# STM32F070CBT6.net
KiCad netlist of a schematic drawn in Altium Designer
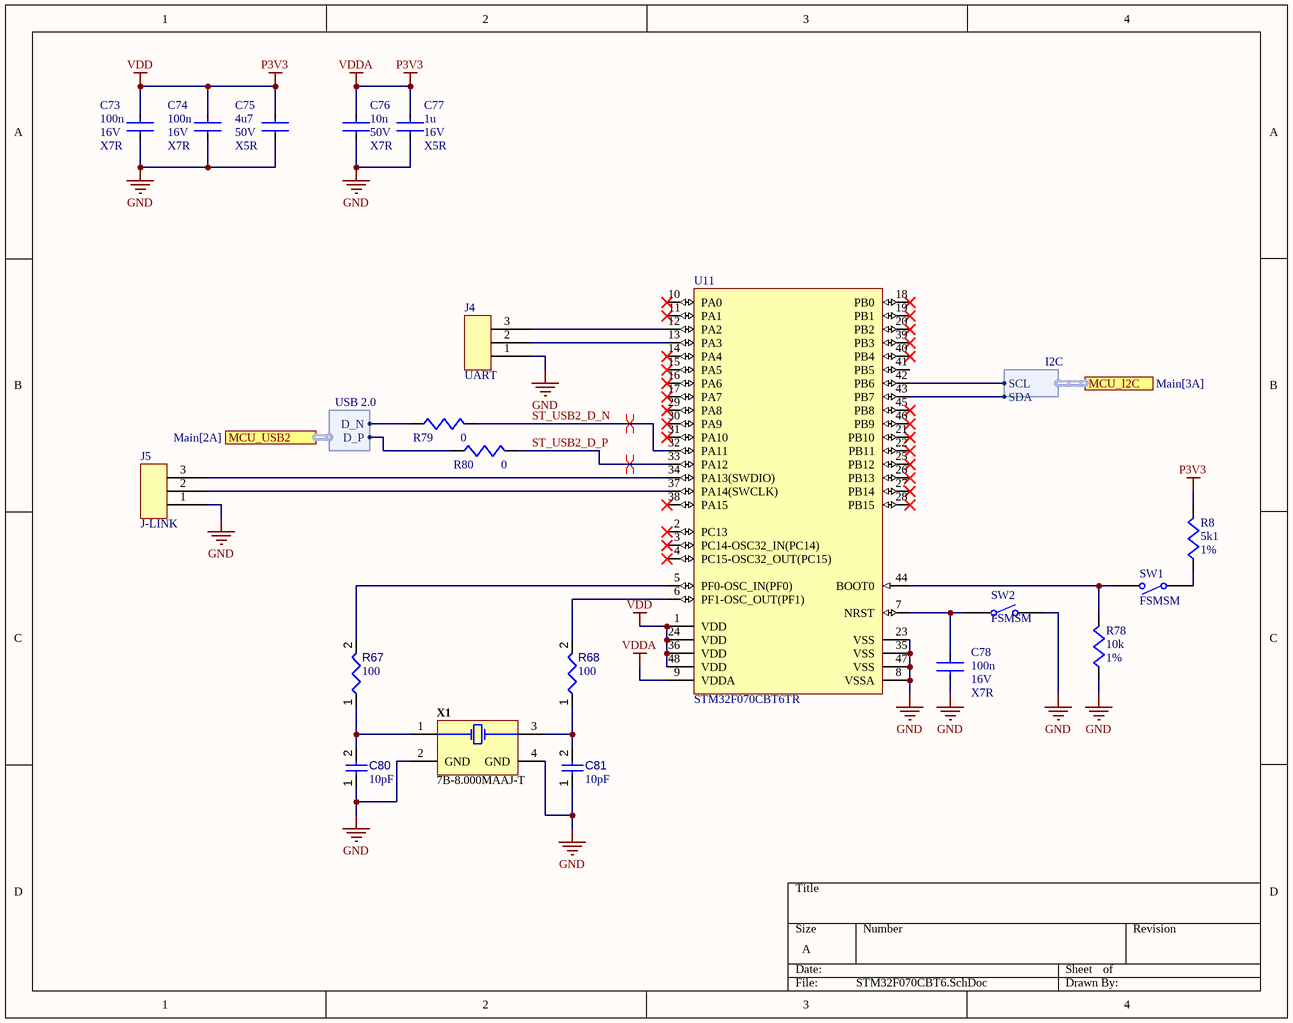
[diagram p0: STM32F070CBT6.SchDoc]

(export (version "E")
  (design (tool "Eeschema 10.0.6"))
  (components
    (comp (ref "C73")
      (value "100n")
      (footprint "CAPC1005X06N")
      (description "16V 100nF X7R ±10% 0402 Multilayer Ceramic Capacitors MLCC - SMD/SMT ROHS")
      (fields
        (field (name "VOLTAGE") "16V")
        (field (name "DIELECTRIC") "X7R")
        (field (name "LCSC PART #") "C1525")
        (field (name "Comment") "100nF 16V 0402")
      )
      (libsource (lib "CWRU Motorsports") (part "Capacitor"))
    )
    (comp (ref "C74")
      (value "100n")
      (footprint "CAPC1005X06N")
      (description "16V 100nF X7R ±10% 0402 Multilayer Ceramic Capacitors MLCC - SMD/SMT ROHS")
      (fields
        (field (name "VOLTAGE") "16V")
        (field (name "DIELECTRIC") "X7R")
        (field (name "LCSC PART #") "C1525")
        (field (name "Comment") "100nF 16V 0402")
      )
      (libsource (lib "CWRU Motorsports") (part "Capacitor"))
    )
    (comp (ref "C75")
      (value "4u7")
      (footprint "CAPC2012X14N")
      (description "50V 4.7uF X5R ±10% 0805 Multilayer Ceramic Capacitors MLCC - SMD/SMT ROHS")
      (fields
        (field (name "VOLTAGE") "50V")
        (field (name "DIELECTRIC") "X5R")
        (field (name "LCSC PART #") "C98192")
        (field (name "Comment") "4.7uF 50V 0805")
      )
      (libsource (lib "CWRU Motorsports") (part "Capacitor"))
    )
    (comp (ref "C76")
      (value "10n")
      (footprint "CAPC1608X08N")
      (description "50V 10nF X7R ±10% 0603 Multilayer Ceramic Capacitors MLCC - SMD/SMT ROHS")
      (fields
        (field (name "VOLTAGE") "50V")
        (field (name "DIELECTRIC") "X7R")
        (field (name "LCSC PART #") "C100042")
        (field (name "Comment") "10n 50V X7R 0603")
      )
      (libsource (lib "CWRU Motorsports") (part "Capacitor"))
    )
    (comp (ref "C77")
      (value "1u")
      (footprint "CAPC1005X06N")
      (description "16V 1uF X5R ±10% 0402 Multilayer Ceramic Capacitors MLCC - SMD/SMT ROHS")
      (fields
        (field (name "VOLTAGE") "16V")
        (field (name "DIELECTRIC") "X5R")
        (field (name "LCSC PART #") "C29266")
        (field (name "Comment") "1uF 16V X5R 0402")
      )
      (libsource (lib "CWRU Motorsports") (part "Capacitor"))
    )
    (comp (ref "C78")
      (value "100n")
      (footprint "CAPC1005X06N")
      (description "16V 100nF X7R ±10% 0402 Multilayer Ceramic Capacitors MLCC - SMD/SMT ROHS")
      (fields
        (field (name "VOLTAGE") "16V")
        (field (name "DIELECTRIC") "X7R")
        (field (name "LCSC PART #") "C1525")
        (field (name "Comment") "100nF 16V 0402")
      )
      (libsource (lib "CWRU Motorsports") (part "Capacitor"))
    )
    (comp (ref "C80")
      (value "10pF")
      (footprint "CAPC1005X55X25ML05T05")
      (description "Chip Capacitor, 10 pF, +/- 5%, 50 V, 0402 (1005 Metric)")
      (fields (field (name "TOLERANCE") "5%") (field (name "Comment") "Capacitor 10 pF +/- 5% 50 V 0402"))
      (libsource (lib "CWRU Motorsports") (part "CAP-NP-2"))
    )
    (comp (ref "C81")
      (value "10pF")
      (footprint "CAPC1005X55X25ML05T05")
      (description "Chip Capacitor, 10 pF, +/- 5%, 50 V, 0402 (1005 Metric)")
      (fields (field (name "TOLERANCE") "5%") (field (name "Comment") "Capacitor 10 pF +/- 5% 50 V 0402"))
      (libsource (lib "CWRU Motorsports") (part "CAP-NP-2"))
    )
    (comp (ref "J4")
      (value "UART")
      (footprint "3x0.1\" Header-Footprint-1")
      (description "3x0.1\" pitch header")
      (libsource (lib "CWRU Motorsports") (part "3x0.1{dblquote} Header-Symbol-1"))
    )
    (comp (ref "J5")
      (value "J-LINK")
      (footprint "3x0.1\" Header-Footprint-1")
      (description "3x0.1\" pitch header")
      (libsource (lib "CWRU Motorsports") (part "3x0.1{dblquote} Header-Symbol-1"))
    )
    (comp (ref "R8")
      (value "5k1")
      (footprint "RESC1508X05M")
      (description "100mW Thick Film Resistors 75V ±100ppm/℃ ±1% 5.1kΩ 0603 Chip Resistor - Surface Mount ROHS")
      (fields
        (field (name "TOLERANCE") "1%")
        (field (name "LCSC PART #") "C105580")
        (field (name "Comment") "5k1 1% 0603")
      )
      (libsource (lib "CWRU Motorsports") (part "Resistor"))
    )
    (comp (ref "R67")
      (value "100")
      (footprint "RESC0402(1005)_L")
      (description "100R 0.063W 1% 0402 (1005 Metric)  SMD")
      (fields (field (name "TOLERANCE") "1%") (field (name "POWER") "63mW"))
      (libsource (lib "CWRU Motorsports") (part "100R2F"))
    )
    (comp (ref "R68")
      (value "100")
      (footprint "RESC0402(1005)_L")
      (description "100R 0.063W 1% 0402 (1005 Metric)  SMD")
      (fields (field (name "TOLERANCE") "1%") (field (name "POWER") "63mW"))
      (libsource (lib "CWRU Motorsports") (part "100R2F"))
    )
    (comp (ref "R78")
      (value "10k")
      (footprint "RESC1005X04M")
      (description "62.5mW Thick Film Resistors 50V ±100ppm/℃ ±1% 10kΩ 0402 Chip Resistor - Surface Mount ROHS")
      (fields
        (field (name "TOLERANCE") "1%")
        (field (name "LCSC PART #") "C60490")
        (field (name "Comment") "10k 1% 0402")
      )
      (libsource (lib "CWRU Motorsports") (part "Resistor"))
    )
    (comp (ref "R79")
      (value "0")
      (footprint "RESC1508X05M")
      (description "62.5mW Thick Film Resistors 50V 0Ω 0402 Chip Resistor - Surface Mount ROHS")
      (fields (field (name "TOLERANCE") "1%") (field (name "LCSC PART #") "C60485"))
      (libsource (lib "CWRU Motorsports") (part "Resistor"))
    )
    (comp (ref "R80")
      (value "0")
      (footprint "RESC1508X05M")
      (description "62.5mW Thick Film Resistors 50V 0Ω 0402 Chip Resistor - Surface Mount ROHS")
      (fields (field (name "TOLERANCE") "1%") (field (name "LCSC PART #") "C60485"))
      (libsource (lib "CWRU Motorsports") (part "Resistor"))
    )
    (comp (ref "SW1")
      (value "FSMSM")
      (footprint "TECO-FSMSM-2_V")
      (description "Switch Tactile OFF (ON) SPST Rectangular Button Gull Wing 0.05A 12VDC SMD Loose Piece")
      (libsource (lib "CWRU Motorsports") (part "SW-SPST-2_C"))
    )
    (comp (ref "SW2")
      (value "FSMSM")
      (footprint "TECO-FSMSM-2_V")
      (description "Switch Tactile OFF (ON) SPST Rectangular Button Gull Wing 0.05A 12VDC SMD Loose Piece")
      (libsource (lib "CWRU Motorsports") (part "SW-SPST-2_C"))
    )
    (comp (ref "U11")
      (value "STM32F070CBT6TR")
      (footprint "STM-LQFP48_N")
      (description "Mainstream ARM Cortex-M0 Value line MCU with 128 Kbytes Flash, 48 MHz CPU, USB")
      (libsource (lib "CWRU Motorsports") (part "MC-ARM-STM32F070-LQFP48"))
    )
    (comp (ref "X1")
      (value "7B-8.000MAAJ-T")
      (footprint "TXC-7B-4_V")
      (description "SMD Seam Sealing Crystal, 8 MHz, +/- 30 ppm, 18 pF, -10 to 70 degC, 4-Pin SMD, RoHS, Tape and Reel")
      (fields (field (name "MANUFACTURER") "TXC") (field (name "TOLERANCE") "30ppm"))
      (libsource (lib "CWRU Motorsports") (part "XTAL-1-3-4"))
    )
  )
  (nets
    (net (code "4") (name "/D_N") (class "Default")
      (node (ref "R79") (pin "1") (pinfunction "1_1") (pintype "passive"))
    )
    (net (code "5") (name "/D_P") (class "Default")
      (node (ref "R80") (pin "1") (pinfunction "1_1") (pintype "passive"))
    )
    (net (code "6") (name "/SCL") (class "Default")
      (node (ref "U11") (pin "42") (pinfunction "PB6_42") (pintype "bidirectional"))
    )
    (net (code "7") (name "/SDA") (class "Default")
      (node (ref "U11") (pin "43") (pinfunction "PB7_43") (pintype "bidirectional"))
    )
    (net (code "8") (name "/ST_USB2_D_N") (class "Default")
      (node (ref "R79") (pin "2") (pinfunction "2_2") (pintype "passive"))
      (node (ref "U11") (pin "32") (pinfunction "PA11_32") (pintype "bidirectional"))
    )
    (net (code "9") (name "/ST_USB2_D_P") (class "Default")
      (node (ref "R80") (pin "2") (pinfunction "2_2") (pintype "passive"))
      (node (ref "U11") (pin "33") (pinfunction "PA12_33") (pintype "bidirectional"))
    )
    (net (code "12") (name "GND") (class "Default")
      (node (ref "C73") (pin "2") (pinfunction "2_2") (pintype "passive"))
      (node (ref "C74") (pin "2") (pinfunction "2_2") (pintype "passive"))
      (node (ref "C75") (pin "2") (pinfunction "2_2") (pintype "passive"))
      (node (ref "C76") (pin "2") (pinfunction "2_2") (pintype "passive"))
      (node (ref "C77") (pin "2") (pinfunction "2_2") (pintype "passive"))
      (node (ref "C78") (pin "1") (pinfunction "1_1") (pintype "passive"))
      (node (ref "C80") (pin "1") (pinfunction "1_1") (pintype "passive"))
      (node (ref "C81") (pin "1") (pinfunction "1_1") (pintype "passive"))
      (node (ref "J4") (pin "1") (pintype "passive"))
      (node (ref "J5") (pin "1") (pintype "passive"))
      (node (ref "R78") (pin "1") (pinfunction "1_1") (pintype "passive"))
      (node (ref "SW2") (pin "2") (pinfunction "2_2") (pintype "passive"))
      (node (ref "U11") (pin "23") (pinfunction "VSS_23") (pintype "power_in"))
      (node (ref "U11") (pin "35") (pinfunction "VSS_35") (pintype "power_in"))
      (node (ref "U11") (pin "47") (pinfunction "VSS_47") (pintype "power_in"))
      (node (ref "U11") (pin "8") (pinfunction "VSSA_8") (pintype "power_in"))
      (node (ref "X1") (pin "2") (pinfunction "GND_2") (pintype "power_in"))
      (node (ref "X1") (pin "4") (pinfunction "GND_4") (pintype "power_in"))
    )
    (net (code "13") (name "Net-(R8-Pad1)") (class "Default")
      (node (ref "R8") (pin "1") (pinfunction "1_1") (pintype "passive"))
      (node (ref "SW1") (pin "1") (pinfunction "1_1") (pintype "passive"))
    )
    (net (code "14") (name "Net-(U11-BOOT0)") (class "Default")
      (node (ref "R78") (pin "2") (pinfunction "2_2") (pintype "passive"))
      (node (ref "SW1") (pin "2") (pinfunction "2_2") (pintype "passive"))
      (node (ref "U11") (pin "44") (pinfunction "BOOT0_44") (pintype "input"))
    )
    (net (code "15") (name "Net-(U11-NRST)") (class "Default")
      (node (ref "C78") (pin "2") (pinfunction "2_2") (pintype "passive"))
      (node (ref "SW2") (pin "1") (pinfunction "1_1") (pintype "passive"))
      (node (ref "U11") (pin "7") (pinfunction "NRST_7") (pintype "bidirectional"))
    )
    (net (code "16") (name "Net-(U11-PA2)") (class "Default")
      (node (ref "J4") (pin "3") (pintype "passive"))
      (node (ref "U11") (pin "12") (pinfunction "PA2_12") (pintype "bidirectional"))
    )
    (net (code "17") (name "Net-(U11-PA3)") (class "Default")
      (node (ref "J4") (pin "2") (pintype "passive"))
      (node (ref "U11") (pin "13") (pinfunction "PA3_13") (pintype "bidirectional"))
    )
    (net (code "18") (name "Net-(U11-PA13(SWDIO))") (class "Default")
      (node (ref "J5") (pin "3") (pintype "passive"))
      (node (ref "U11") (pin "34") (pinfunction "PA13(SWDIO)_34") (pintype "bidirectional"))
    )
    (net (code "19") (name "Net-(U11-PA14(SWCLK))") (class "Default")
      (node (ref "J5") (pin "2") (pintype "passive"))
      (node (ref "U11") (pin "37") (pinfunction "PA14(SWCLK)_37") (pintype "bidirectional"))
    )
    (net (code "20") (name "Net-(U11-PF0-OSC_IN(PF0))") (class "Default")
      (node (ref "R67") (pin "2") (pinfunction "2_2") (pintype "passive"))
      (node (ref "U11") (pin "5") (pinfunction "PF0-OSC_IN(PF0)_5") (pintype "bidirectional"))
    )
    (net (code "21") (name "Net-(U11-PF1-OSC_OUT(PF1))") (class "Default")
      (node (ref "R68") (pin "2") (pinfunction "2_2") (pintype "passive"))
      (node (ref "U11") (pin "6") (pinfunction "PF1-OSC_OUT(PF1)_6") (pintype "bidirectional"))
    )
    (net (code "22") (name "Net-(X1-X1)") (class "Default")
      (node (ref "C80") (pin "2") (pinfunction "2_2") (pintype "passive"))
      (node (ref "R67") (pin "1") (pinfunction "1_1") (pintype "passive"))
      (node (ref "X1") (pin "1") (pinfunction "X1_1") (pintype "passive"))
    )
    (net (code "23") (name "Net-(X1-X2)") (class "Default")
      (node (ref "C81") (pin "2") (pinfunction "2_2") (pintype "passive"))
      (node (ref "R68") (pin "1") (pinfunction "1_1") (pintype "passive"))
      (node (ref "X1") (pin "3") (pinfunction "X2_3") (pintype "passive"))
    )
    (net (code "24") (name "P3V3") (class "Default")
      (node (ref "C73") (pin "1") (pinfunction "1_1") (pintype "passive"))
      (node (ref "C74") (pin "1") (pinfunction "1_1") (pintype "passive"))
      (node (ref "C75") (pin "1") (pinfunction "1_1") (pintype "passive"))
      (node (ref "C76") (pin "1") (pinfunction "1_1") (pintype "passive"))
      (node (ref "C77") (pin "1") (pinfunction "1_1") (pintype "passive"))
      (node (ref "R8") (pin "2") (pinfunction "2_2") (pintype "passive"))
      (node (ref "U11") (pin "1") (pinfunction "VDD_1") (pintype "power_in"))
      (node (ref "U11") (pin "24") (pinfunction "VDD_24") (pintype "power_in"))
      (node (ref "U11") (pin "36") (pinfunction "VDD_36") (pintype "power_in"))
      (node (ref "U11") (pin "48") (pinfunction "VDD_48") (pintype "power_in"))
      (node (ref "U11") (pin "9") (pinfunction "VDDA_9") (pintype "power_in"))
    )
    (net (code "25") (name "unconnected-(U11-PA0-Pad10)") (class "Default")
      (node (ref "U11") (pin "10") (pinfunction "PA0_10") (pintype "bidirectional+no_connect"))
    )
    (net (code "26") (name "unconnected-(U11-PA1-Pad11)") (class "Default")
      (node (ref "U11") (pin "11") (pinfunction "PA1_11") (pintype "bidirectional+no_connect"))
    )
    (net (code "27") (name "unconnected-(U11-PA4-Pad14)") (class "Default")
      (node (ref "U11") (pin "14") (pinfunction "PA4_14") (pintype "bidirectional+no_connect"))
    )
    (net (code "28") (name "unconnected-(U11-PA5-Pad15)") (class "Default")
      (node (ref "U11") (pin "15") (pinfunction "PA5_15") (pintype "bidirectional+no_connect"))
    )
    (net (code "29") (name "unconnected-(U11-PA6-Pad16)") (class "Default")
      (node (ref "U11") (pin "16") (pinfunction "PA6_16") (pintype "bidirectional+no_connect"))
    )
    (net (code "30") (name "unconnected-(U11-PA7-Pad17)") (class "Default")
      (node (ref "U11") (pin "17") (pinfunction "PA7_17") (pintype "bidirectional+no_connect"))
    )
    (net (code "31") (name "unconnected-(U11-PA8-Pad29)") (class "Default")
      (node (ref "U11") (pin "29") (pinfunction "PA8_29") (pintype "bidirectional+no_connect"))
    )
    (net (code "32") (name "unconnected-(U11-PA9-Pad30)") (class "Default")
      (node (ref "U11") (pin "30") (pinfunction "PA9_30") (pintype "bidirectional+no_connect"))
    )
    (net (code "33") (name "unconnected-(U11-PA10-Pad31)") (class "Default")
      (node (ref "U11") (pin "31") (pinfunction "PA10_31") (pintype "bidirectional+no_connect"))
    )
    (net (code "34") (name "unconnected-(U11-PA15-Pad38)") (class "Default")
      (node (ref "U11") (pin "38") (pinfunction "PA15_38") (pintype "bidirectional+no_connect"))
    )
    (net (code "35") (name "unconnected-(U11-PB0-Pad18)") (class "Default")
      (node (ref "U11") (pin "18") (pinfunction "PB0_18") (pintype "bidirectional+no_connect"))
    )
    (net (code "36") (name "unconnected-(U11-PB1-Pad19)") (class "Default")
      (node (ref "U11") (pin "19") (pinfunction "PB1_19") (pintype "bidirectional+no_connect"))
    )
    (net (code "37") (name "unconnected-(U11-PB2-Pad20)") (class "Default")
      (node (ref "U11") (pin "20") (pinfunction "PB2_20") (pintype "bidirectional+no_connect"))
    )
    (net (code "38") (name "unconnected-(U11-PB3-Pad39)") (class "Default")
      (node (ref "U11") (pin "39") (pinfunction "PB3_39") (pintype "bidirectional+no_connect"))
    )
    (net (code "39") (name "unconnected-(U11-PB4-Pad40)") (class "Default")
      (node (ref "U11") (pin "40") (pinfunction "PB4_40") (pintype "bidirectional+no_connect"))
    )
    (net (code "40") (name "unconnected-(U11-PB5-Pad41)") (class "Default")
      (node (ref "U11") (pin "41") (pinfunction "PB5_41") (pintype "bidirectional"))
    )
    (net (code "41") (name "unconnected-(U11-PB8-Pad45)") (class "Default")
      (node (ref "U11") (pin "45") (pinfunction "PB8_45") (pintype "bidirectional+no_connect"))
    )
    (net (code "42") (name "unconnected-(U11-PB9-Pad46)") (class "Default")
      (node (ref "U11") (pin "46") (pinfunction "PB9_46") (pintype "bidirectional+no_connect"))
    )
    (net (code "43") (name "unconnected-(U11-PB10-Pad21)") (class "Default")
      (node (ref "U11") (pin "21") (pinfunction "PB10_21") (pintype "bidirectional+no_connect"))
    )
    (net (code "44") (name "unconnected-(U11-PB11-Pad22)") (class "Default")
      (node (ref "U11") (pin "22") (pinfunction "PB11_22") (pintype "bidirectional+no_connect"))
    )
    (net (code "45") (name "unconnected-(U11-PB12-Pad25)") (class "Default")
      (node (ref "U11") (pin "25") (pinfunction "PB12_25") (pintype "bidirectional+no_connect"))
    )
    (net (code "46") (name "unconnected-(U11-PB13-Pad26)") (class "Default")
      (node (ref "U11") (pin "26") (pinfunction "PB13_26") (pintype "bidirectional+no_connect"))
    )
    (net (code "47") (name "unconnected-(U11-PB14-Pad27)") (class "Default")
      (node (ref "U11") (pin "27") (pinfunction "PB14_27") (pintype "bidirectional+no_connect"))
    )
    (net (code "48") (name "unconnected-(U11-PB15-Pad28)") (class "Default")
      (node (ref "U11") (pin "28") (pinfunction "PB15_28") (pintype "bidirectional+no_connect"))
    )
    (net (code "49") (name "unconnected-(U11-PC13-Pad2)") (class "Default")
      (node (ref "U11") (pin "2") (pinfunction "PC13_2") (pintype "bidirectional+no_connect"))
    )
    (net (code "50") (name "unconnected-(U11-PC14-OSC32_IN(PC14)-Pad3)") (class "Default")
      (node (ref "U11") (pin "3") (pinfunction "PC14-OSC32_IN(PC14)_3") (pintype "bidirectional+no_connect"))
    )
    (net (code "51") (name "unconnected-(U11-PC15-OSC32_OUT(PC15)-Pad4)") (class "Default")
      (node (ref "U11") (pin "4") (pinfunction "PC15-OSC32_OUT(PC15)_4") (pintype "bidirectional+no_connect"))
    )
  )
)
